# Helm.net
KiCad netlist of a schematic drawn in EAGLE
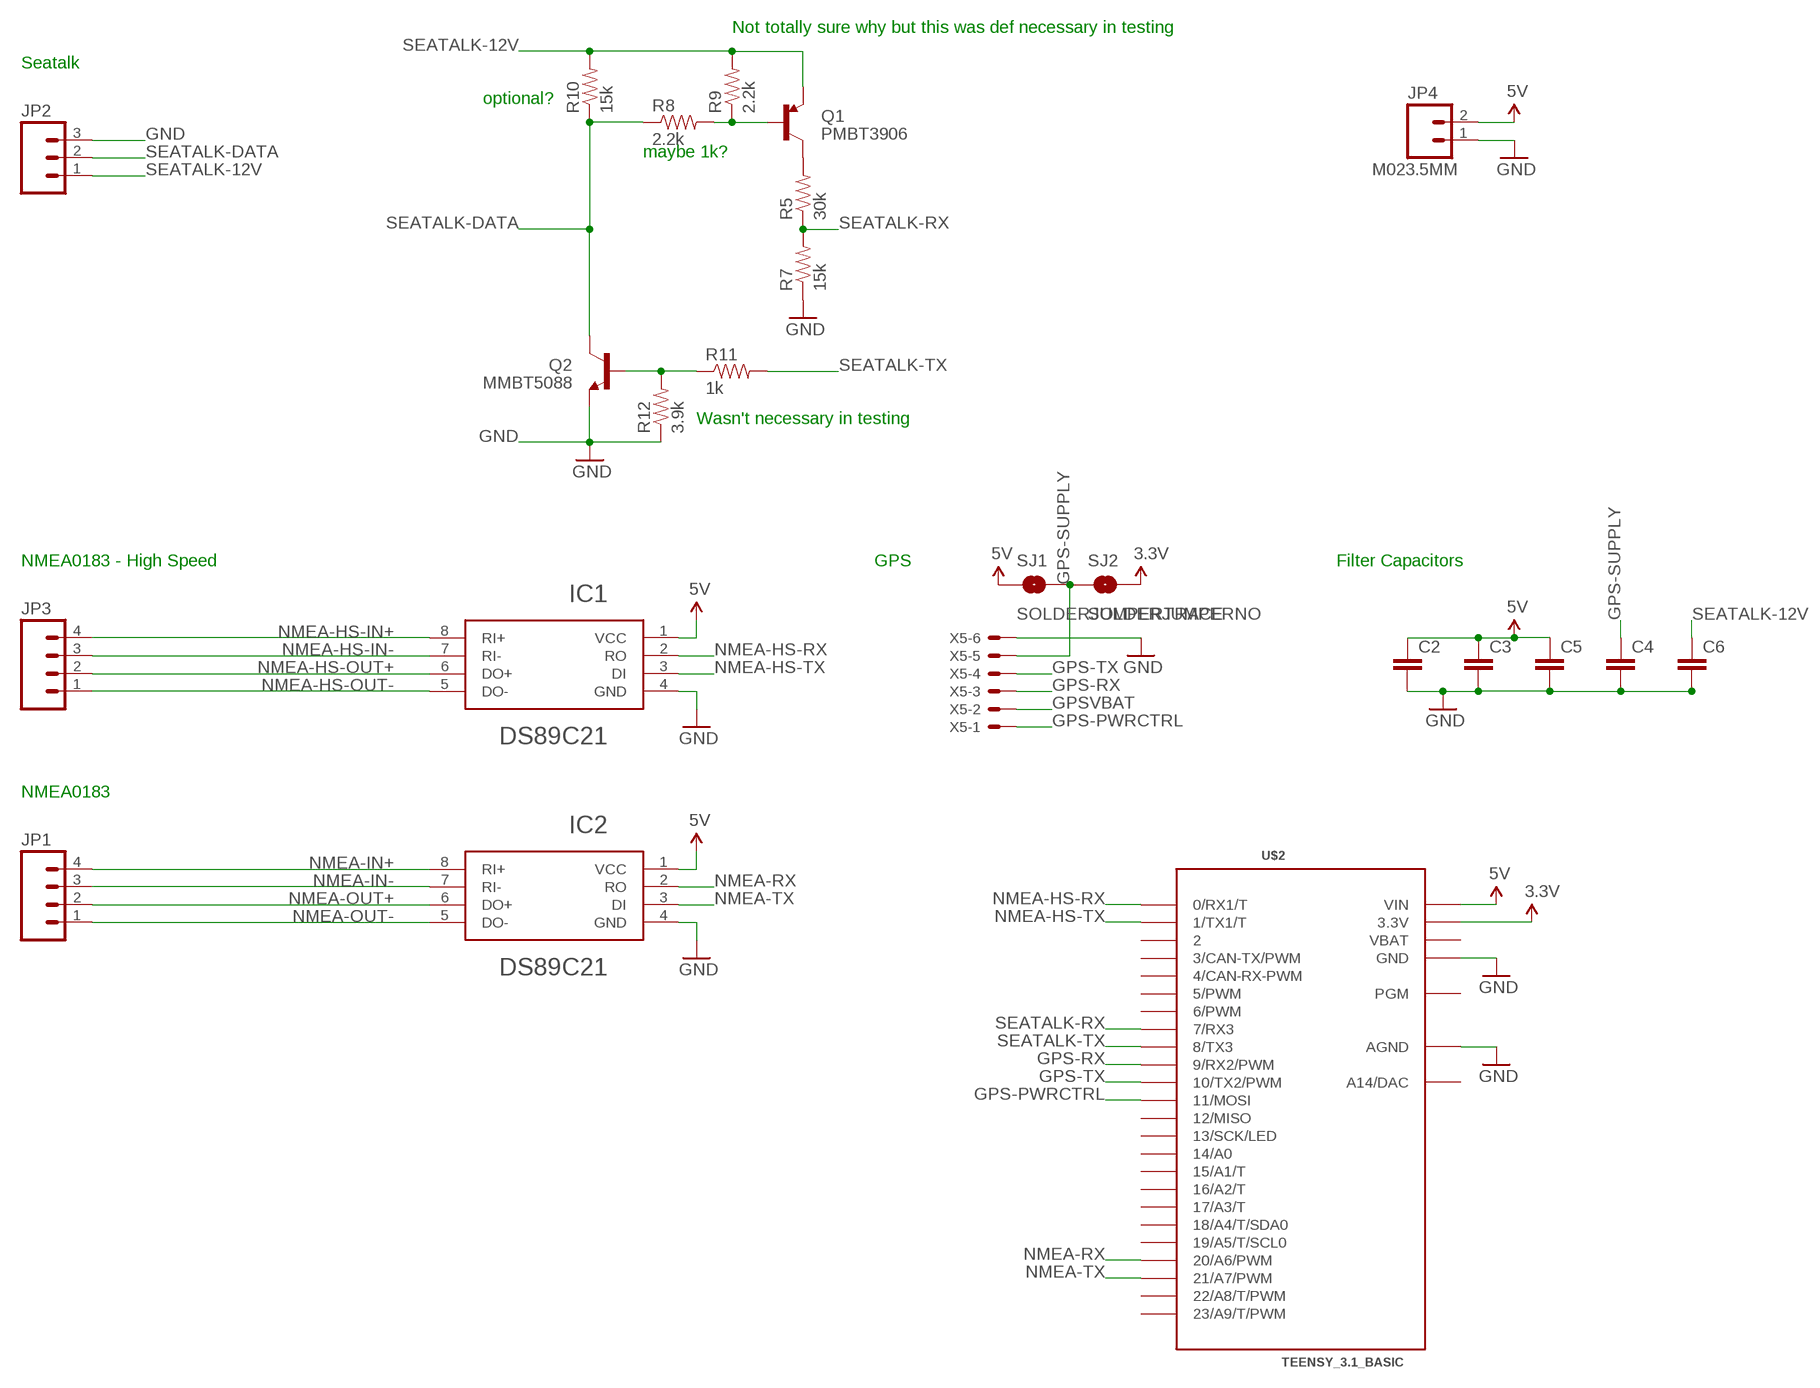
[diagram p0: schematic, sheet 1]

(export (version "E")
  (design (tool "Eeschema 10.0.6"))
  (components
    (comp (ref "C2")
      (value "CAP0805")
      (footprint "eagle-import:0805")
      (libsource (lib "eagle-import") (part "CAP0805"))
    )
    (comp (ref "C3")
      (value "CAP0805")
      (footprint "eagle-import:0805")
      (libsource (lib "eagle-import") (part "CAP0805"))
    )
    (comp (ref "C4")
      (value "CAP0805")
      (footprint "eagle-import:0805")
      (libsource (lib "eagle-import") (part "CAP0805"))
    )
    (comp (ref "C5")
      (value "CAP0805")
      (footprint "eagle-import:0805")
      (libsource (lib "eagle-import") (part "CAP0805"))
    )
    (comp (ref "C6")
      (value "CAP0805")
      (footprint "eagle-import:0805")
      (libsource (lib "eagle-import") (part "CAP0805"))
    )
    (comp (ref "IC1")
      (value "DS89C21")
      (footprint "eagle-import:SO08")
      (libsource (lib "eagle-import") (part "DS89C21"))
    )
    (comp (ref "IC2")
      (value "DS89C21")
      (footprint "eagle-import:SO08")
      (libsource (lib "eagle-import") (part "DS89C21"))
    )
    (comp (ref "JP1")
      (value "M04SCREW")
      (footprint "eagle-import:SCREWTERMINAL-3.5MM-4")
      (libsource (lib "eagle-import") (part "M04SCREW"))
    )
    (comp (ref "JP2")
      (value "M03SCREW")
      (footprint "eagle-import:SCREWTERMINAL-3.5MM-3")
      (libsource (lib "eagle-import") (part "M03SCREW"))
    )
    (comp (ref "JP3")
      (value "M04SCREW")
      (footprint "eagle-import:SCREWTERMINAL-3.5MM-4")
      (libsource (lib "eagle-import") (part "M04SCREW"))
    )
    (comp (ref "JP4")
      (value "M023.5MM")
      (footprint "eagle-import:SCREWTERMINAL-3.5MM-2")
      (libsource (lib "eagle-import") (part "M023.5MM"))
    )
    (comp (ref "Q1")
      (value "PMBT3906")
      (footprint "eagle-import:SOT23-3")
      (libsource (lib "eagle-import") (part "TRANSISTOR_PNPPMBT3906"))
    )
    (comp (ref "Q2")
      (value "MMBT5088")
      (footprint "eagle-import:SOT23-3")
      (libsource (lib "eagle-import") (part "TRANSISTOR_NPNMMBT5088"))
    )
    (comp (ref "R5")
      (value "30k")
      (footprint "eagle-import:0603-RES")
      (libsource (lib "eagle-import") (part "RESISTOR0603-RES"))
    )
    (comp (ref "R7")
      (value "15k")
      (footprint "eagle-import:0603-RES")
      (libsource (lib "eagle-import") (part "RESISTOR0603-RES"))
    )
    (comp (ref "R8")
      (value "2.2k")
      (footprint "eagle-import:0603-RES")
      (libsource (lib "eagle-import") (part "RESISTOR0603-RES"))
    )
    (comp (ref "R9")
      (value "2.2k")
      (footprint "eagle-import:0603-RES")
      (libsource (lib "eagle-import") (part "RESISTOR0603-RES"))
    )
    (comp (ref "R10")
      (value "15k")
      (footprint "eagle-import:0603-RES")
      (libsource (lib "eagle-import") (part "RESISTOR0603-RES"))
    )
    (comp (ref "R11")
      (value "1k")
      (footprint "eagle-import:0603-RES")
      (libsource (lib "eagle-import") (part "RESISTOR0603-RES"))
    )
    (comp (ref "R12")
      (value "3.9k")
      (footprint "eagle-import:0603-RES")
      (libsource (lib "eagle-import") (part "RESISTOR0603-RES"))
    )
    (comp (ref "SJ1")
      (value "SOLDERJUMPERTRACE")
      (footprint "eagle-import:SJ_2S-TRACE")
      (libsource (lib "eagle-import") (part "SOLDERJUMPERTRACE"))
    )
    (comp (ref "SJ2")
      (value "SOLDERJUMPERNO")
      (footprint "eagle-import:SJ_2S-NO")
      (libsource (lib "eagle-import") (part "SOLDERJUMPERNO"))
    )
    (comp (ref "U$2")
      (value "TEENSY_3.1_BASIC")
      (footprint "eagle-import:TEENSY_3.1_BASIC")
      (libsource (lib "eagle-import") (part "TEENSY_3.1_BASIC"))
    )
    (comp (ref "X5")
      (value "SM06B-SRSS-TB")
      (footprint "eagle-import:SM06B-SRSS-TB")
      (libsource (lib "eagle-import") (part "?M06B-SRSS-TBS"))
    )
  )
  (nets
    (net (code "1") (name "/GPS-PWRCTRL") (class "Default")
      (node (ref "U$2") (pin "11") (pinfunction "11/MOSI_11") (pintype "bidirectional"))
      (node (ref "X5") (pin "1") (pinfunction "S_1") (pintype "passive"))
    )
    (net (code "2") (name "/GPS-RX") (class "Default")
      (node (ref "U$2") (pin "9") (pinfunction "9/RX2/PWM_9") (pintype "bidirectional"))
      (node (ref "X5") (pin "3") (pinfunction "S_3") (pintype "passive"))
    )
    (net (code "3") (name "/GPS-SUPPLY") (class "Default")
      (node (ref "C4") (pin "1") (pinfunction "1_1") (pintype "passive"))
      (node (ref "SJ1") (pin "2") (pinfunction "2_2") (pintype "passive"))
      (node (ref "SJ2") (pin "1") (pinfunction "1_1") (pintype "passive"))
      (node (ref "X5") (pin "5") (pinfunction "S_5") (pintype "passive"))
    )
    (net (code "4") (name "/GPS-TX") (class "Default")
      (node (ref "U$2") (pin "10") (pinfunction "10/TX2/PWM_10") (pintype "bidirectional"))
      (node (ref "X5") (pin "4") (pinfunction "S_4") (pintype "passive"))
    )
    (net (code "5") (name "/GPSVBAT") (class "Default")
      (node (ref "X5") (pin "2") (pinfunction "S_2") (pintype "passive"))
    )
    (net (code "6") (name "/NMEA-HS-IN+") (class "Default")
      (node (ref "IC1") (pin "8") (pinfunction "RI+_8") (pintype "input"))
      (node (ref "JP3") (pin "4") (pinfunction "4_4") (pintype "passive"))
    )
    (net (code "7") (name "/NMEA-HS-IN-") (class "Default")
      (node (ref "IC1") (pin "7") (pinfunction "RI-_7") (pintype "input"))
      (node (ref "JP3") (pin "3") (pinfunction "3_3") (pintype "passive"))
    )
    (net (code "8") (name "/NMEA-HS-OUT+") (class "Default")
      (node (ref "IC1") (pin "6") (pinfunction "DO+_6") (pintype "output"))
      (node (ref "JP3") (pin "2") (pinfunction "2_2") (pintype "passive"))
    )
    (net (code "9") (name "/NMEA-HS-OUT-") (class "Default")
      (node (ref "IC1") (pin "5") (pinfunction "DO-_5") (pintype "output"))
      (node (ref "JP3") (pin "1") (pinfunction "1_1") (pintype "passive"))
    )
    (net (code "10") (name "/NMEA-HS-RX") (class "Default")
      (node (ref "IC1") (pin "2") (pinfunction "RO_2") (pintype "output"))
      (node (ref "U$2") (pin "0") (pinfunction "0/RX1/T_0") (pintype "bidirectional"))
    )
    (net (code "11") (name "/NMEA-HS-TX") (class "Default")
      (node (ref "IC1") (pin "3") (pinfunction "DI_3") (pintype "input"))
      (node (ref "U$2") (pin "1") (pinfunction "1/TX1/T_1") (pintype "bidirectional"))
    )
    (net (code "12") (name "/NMEA-IN+") (class "Default")
      (node (ref "IC2") (pin "8") (pinfunction "RI+_8") (pintype "input"))
      (node (ref "JP1") (pin "4") (pinfunction "4_4") (pintype "passive"))
    )
    (net (code "13") (name "/NMEA-IN-") (class "Default")
      (node (ref "IC2") (pin "7") (pinfunction "RI-_7") (pintype "input"))
      (node (ref "JP1") (pin "3") (pinfunction "3_3") (pintype "passive"))
    )
    (net (code "14") (name "/NMEA-OUT+") (class "Default")
      (node (ref "IC2") (pin "6") (pinfunction "DO+_6") (pintype "output"))
      (node (ref "JP1") (pin "2") (pinfunction "2_2") (pintype "passive"))
    )
    (net (code "15") (name "/NMEA-OUT-") (class "Default")
      (node (ref "IC2") (pin "5") (pinfunction "DO-_5") (pintype "output"))
      (node (ref "JP1") (pin "1") (pinfunction "1_1") (pintype "passive"))
    )
    (net (code "16") (name "/NMEA-RX") (class "Default")
      (node (ref "IC2") (pin "2") (pinfunction "RO_2") (pintype "output"))
      (node (ref "U$2") (pin "20/A6") (pinfunction "20/A6/PWM_20/A6") (pintype "bidirectional"))
    )
    (net (code "17") (name "/NMEA-TX") (class "Default")
      (node (ref "IC2") (pin "3") (pinfunction "DI_3") (pintype "input"))
      (node (ref "U$2") (pin "21/A7") (pinfunction "21/A7/PWM_21/A7") (pintype "bidirectional"))
    )
    (net (code "18") (name "/SEATALK-12V") (class "Default")
      (node (ref "C6") (pin "1") (pinfunction "1_1") (pintype "passive"))
      (node (ref "JP2") (pin "1") (pinfunction "1_1") (pintype "passive"))
      (node (ref "Q1") (pin "2") (pinfunction "E_2") (pintype "passive"))
      (node (ref "R10") (pin "2") (pinfunction "2_2") (pintype "passive"))
      (node (ref "R9") (pin "2") (pinfunction "2_2") (pintype "passive"))
    )
    (net (code "19") (name "/SEATALK-DATA") (class "Default")
      (node (ref "JP2") (pin "2") (pinfunction "2_2") (pintype "passive"))
      (node (ref "Q2") (pin "3") (pinfunction "C_3") (pintype "passive"))
      (node (ref "R10") (pin "1") (pinfunction "1_1") (pintype "passive"))
      (node (ref "R8") (pin "1") (pinfunction "1_1") (pintype "passive"))
    )
    (net (code "20") (name "/SEATALK-RX") (class "Default")
      (node (ref "R5") (pin "1") (pinfunction "1_1") (pintype "passive"))
      (node (ref "R7") (pin "2") (pinfunction "2_2") (pintype "passive"))
      (node (ref "U$2") (pin "7") (pinfunction "7/RX3_7") (pintype "bidirectional"))
    )
    (net (code "21") (name "/SEATALK-TX") (class "Default")
      (node (ref "R11") (pin "2") (pinfunction "2_2") (pintype "passive"))
      (node (ref "U$2") (pin "8") (pinfunction "8/TX3_8") (pintype "bidirectional"))
    )
    (net (code "22") (name "/VBAT") (class "Default")
      (node (ref "U$2") (pin "VBAT") (pinfunction "VBAT_VBAT") (pintype "power_in"))
    )
    (net (code "23") (name "3.3V") (class "Default")
      (node (ref "SJ2") (pin "2") (pinfunction "2_2") (pintype "passive"))
      (node (ref "U$2") (pin "3.3V") (pinfunction "3.3V_3.3V") (pintype "power_in"))
      (node (ref "U$2") (pin "3.3V1") (pinfunction "3.3V_3.3V1") (pintype "power_in"))
    )
    (net (code "24") (name "5V") (class "Default")
      (node (ref "C2") (pin "1") (pinfunction "1_1") (pintype "passive"))
      (node (ref "C3") (pin "1") (pinfunction "1_1") (pintype "passive"))
      (node (ref "C5") (pin "1") (pinfunction "1_1") (pintype "passive"))
      (node (ref "IC1") (pin "1") (pinfunction "VCC_1") (pintype "power_in"))
      (node (ref "IC2") (pin "1") (pinfunction "VCC_1") (pintype "power_in"))
      (node (ref "JP4") (pin "2") (pinfunction "2_2") (pintype "passive"))
      (node (ref "SJ1") (pin "1") (pinfunction "1_1") (pintype "passive"))
      (node (ref "U$2") (pin "VIN") (pinfunction "VIN_VIN") (pintype "power_in"))
    )
    (net (code "25") (name "GND") (class "Default")
      (node (ref "C2") (pin "2") (pinfunction "2_2") (pintype "passive"))
      (node (ref "C3") (pin "2") (pinfunction "2_2") (pintype "passive"))
      (node (ref "C4") (pin "2") (pinfunction "2_2") (pintype "passive"))
      (node (ref "C5") (pin "2") (pinfunction "2_2") (pintype "passive"))
      (node (ref "C6") (pin "2") (pinfunction "2_2") (pintype "passive"))
      (node (ref "IC1") (pin "4") (pinfunction "GND_4") (pintype "power_in"))
      (node (ref "IC2") (pin "4") (pinfunction "GND_4") (pintype "power_in"))
      (node (ref "JP2") (pin "3") (pinfunction "3_3") (pintype "passive"))
      (node (ref "JP4") (pin "1") (pinfunction "1_1") (pintype "passive"))
      (node (ref "Q2") (pin "2") (pinfunction "E_2") (pintype "passive"))
      (node (ref "R12") (pin "1") (pinfunction "1_1") (pintype "passive"))
      (node (ref "R7") (pin "1") (pinfunction "1_1") (pintype "passive"))
      (node (ref "U$2") (pin "AGND") (pinfunction "AGND_AGND") (pintype "power_in"))
      (node (ref "U$2") (pin "GND") (pinfunction "GND_GND") (pintype "power_in"))
      (node (ref "U$2") (pin "GND1") (pinfunction "GND_GND1") (pintype "power_in"))
      (node (ref "X5") (pin "6") (pinfunction "S_6") (pintype "passive"))
    )
    (net (code "26") (name "Net-(Q1-B)") (class "Default")
      (node (ref "Q1") (pin "1") (pinfunction "B_1") (pintype "passive"))
      (node (ref "R8") (pin "2") (pinfunction "2_2") (pintype "passive"))
      (node (ref "R9") (pin "1") (pinfunction "1_1") (pintype "passive"))
    )
    (net (code "27") (name "Net-(Q1-C)") (class "Default")
      (node (ref "Q1") (pin "3") (pinfunction "C_3") (pintype "passive"))
      (node (ref "R5") (pin "2") (pinfunction "2_2") (pintype "passive"))
    )
    (net (code "28") (name "Net-(Q2-B)") (class "Default")
      (node (ref "Q2") (pin "1") (pinfunction "B_1") (pintype "passive"))
      (node (ref "R11") (pin "1") (pinfunction "1_1") (pintype "passive"))
      (node (ref "R12") (pin "2") (pinfunction "2_2") (pintype "passive"))
    )
    (net (code "29") (name "unconnected-(U$2-3{slash}CAN-TX{slash}PWM-Pad3)") (class "Default")
      (node (ref "U$2") (pin "3") (pinfunction "3/CAN-TX/PWM_3") (pintype "bidirectional"))
    )
    (net (code "30") (name "unconnected-(U$2-4{slash}CAN-RX-PWM-Pad4)") (class "Default")
      (node (ref "U$2") (pin "4") (pinfunction "4/CAN-RX-PWM_4") (pintype "bidirectional"))
    )
    (net (code "31") (name "unconnected-(U$2-5{slash}PWM-Pad5)") (class "Default")
      (node (ref "U$2") (pin "5") (pinfunction "5/PWM_5") (pintype "bidirectional"))
    )
    (net (code "32") (name "unconnected-(U$2-6{slash}PWM-Pad6)") (class "Default")
      (node (ref "U$2") (pin "6") (pinfunction "6/PWM_6") (pintype "bidirectional"))
    )
    (net (code "33") (name "unconnected-(U$2-12{slash}MISO-Pad12)") (class "Default")
      (node (ref "U$2") (pin "12") (pinfunction "12/MISO_12") (pintype "bidirectional"))
    )
    (net (code "34") (name "unconnected-(U$2-13{slash}SCK{slash}LED-Pad13)") (class "Default")
      (node (ref "U$2") (pin "13") (pinfunction "13/SCK/LED_13") (pintype "bidirectional"))
    )
    (net (code "35") (name "unconnected-(U$2-15{slash}A1{slash}T-Pad15{slash}A1)") (class "Default")
      (node (ref "U$2") (pin "15/A1") (pinfunction "15/A1/T_15/A1") (pintype "bidirectional"))
    )
    (net (code "36") (name "unconnected-(U$2-16{slash}A2{slash}T-Pad16{slash}A2)") (class "Default")
      (node (ref "U$2") (pin "16/A2") (pinfunction "16/A2/T_16/A2") (pintype "bidirectional"))
    )
    (net (code "37") (name "unconnected-(U$2-17{slash}A3{slash}T-Pad17{slash}A3)") (class "Default")
      (node (ref "U$2") (pin "17/A3") (pinfunction "17/A3/T_17/A3") (pintype "bidirectional"))
    )
    (net (code "38") (name "unconnected-(U$2-18{slash}A4{slash}T{slash}SDA0-Pad18{slash}A4)") (class "Default")
      (node (ref "U$2") (pin "18/A4") (pinfunction "18/A4/T/SDA0_18/A4") (pintype "bidirectional"))
    )
    (net (code "39") (name "unconnected-(U$2-19{slash}A5{slash}T{slash}SCL0-Pad19{slash}A5)") (class "Default")
      (node (ref "U$2") (pin "19/A5") (pinfunction "19/A5/T/SCL0_19/A5") (pintype "bidirectional"))
    )
    (net (code "40") (name "unconnected-(U$2-22{slash}A8{slash}T{slash}PWM-Pad22{slash}A8)") (class "Default")
      (node (ref "U$2") (pin "22/A8") (pinfunction "22/A8/T/PWM_22/A8") (pintype "bidirectional"))
    )
    (net (code "41") (name "unconnected-(U$2-23{slash}A9{slash}T{slash}PWM-Pad23{slash}A9)") (class "Default")
      (node (ref "U$2") (pin "23/A9") (pinfunction "23/A9/T/PWM_23/A9") (pintype "bidirectional"))
    )
    (net (code "42") (name "unconnected-(U$2-A14{slash}DAC-PadA14)") (class "Default")
      (node (ref "U$2") (pin "A14") (pinfunction "A14/DAC_A14") (pintype "bidirectional"))
    )
    (net (code "43") (name "unconnected-(U$2-Pad2)") (class "Default")
      (node (ref "U$2") (pin "2") (pinfunction "2_2") (pintype "bidirectional"))
    )
    (net (code "44") (name "unconnected-(U$2-Pad14{slash}A0)") (class "Default")
      (node (ref "U$2") (pin "14/A0") (pinfunction "14/A0_14/A0") (pintype "bidirectional"))
    )
    (net (code "45") (name "unconnected-(U$2-PadPGM)") (class "Default")
      (node (ref "U$2") (pin "PGM") (pinfunction "PGM_PGM") (pintype "bidirectional"))
    )
  )
)
